# ADC.net
KiCad netlist of a schematic drawn in Altium Designer
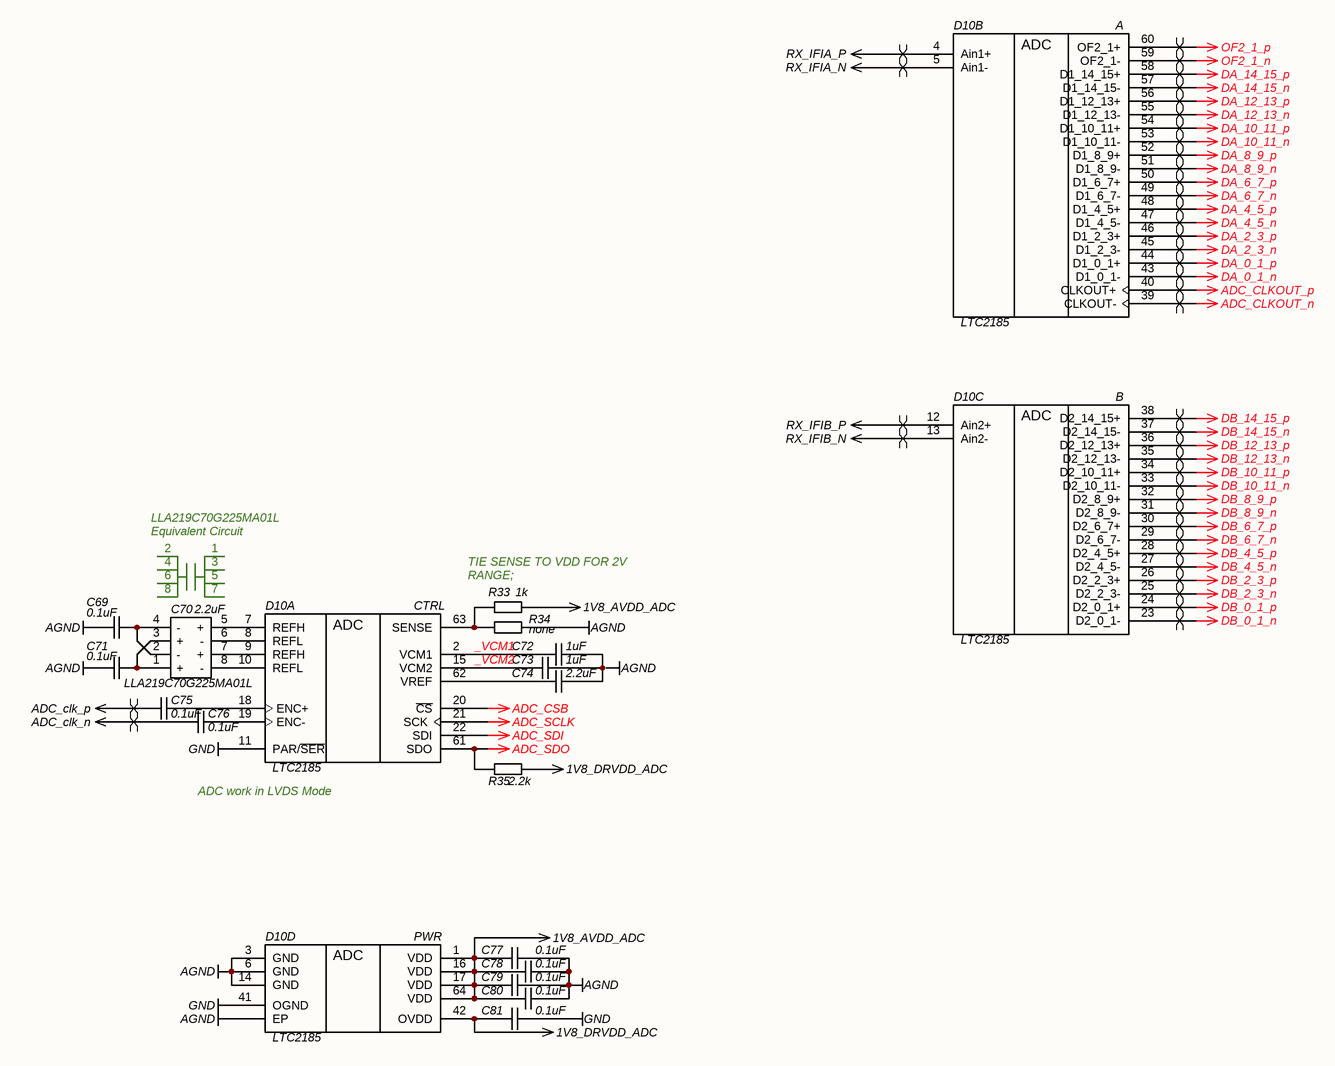
[diagram p0: ADC.SchDoc]

(export (version "E")
  (design (tool "Eeschema 10.0.6"))
  (components
    (comp (ref "C69")
      (value "0.1uF")
      (footprint "C0402")
      (description "SMD Capacitor")
      (fields (field (name "MANUFACTURER") "Murata") (field (name "TOLERANCE") "10%"))
      (libsource (lib "Kintex_SDR") (part "CAP"))
    )
    (comp (ref "C70")
      (value "LLA219C70G225MA01L")
      (footprint "DBLib:Murata_LLA219-0_1_MFG")
      (description "0805 2.2 uF 4 V ±20 % Tolerance X7S Surface Mount Multilayer Ceramic Capacitor")
      (fields
        (field (name "MANUFACTURER") "Murata")
        (field (name "TOLERANCE") "20%")
        (field (name "ALTIUM_VALUE") "2.2uF")
      )
      (libsource (lib "DBLib") (part "LLA219C70G225M"))
    )
    (comp (ref "C71")
      (value "0.1uF")
      (footprint "C0402")
      (description "SMD Capacitor")
      (fields (field (name "MANUFACTURER") "Murata") (field (name "TOLERANCE") "10%"))
      (libsource (lib "Kintex_SDR") (part "CAP"))
    )
    (comp (ref "C72")
      (value "1uF")
      (footprint "C0402")
      (description "SMD Capacitor")
      (fields (field (name "MANUFACTURER") "Murata") (field (name "TOLERANCE") "10%"))
      (libsource (lib "Kintex_SDR") (part "CAP"))
    )
    (comp (ref "C73")
      (value "1uF")
      (footprint "C0402")
      (description "SMD Capacitor")
      (fields (field (name "MANUFACTURER") "Murata") (field (name "TOLERANCE") "10%"))
      (libsource (lib "Kintex_SDR") (part "CAP"))
    )
    (comp (ref "C74")
      (value "2.2uF")
      (footprint "C0603")
      (description "SMD Capacitor")
      (fields (field (name "MANUFACTURER") "Murata") (field (name "TOLERANCE") "10%"))
      (libsource (lib "Kintex_SDR") (part "CAP"))
    )
    (comp (ref "C75")
      (value "0.1uF")
      (footprint "C0402")
      (description "SMD Capacitor")
      (fields (field (name "MANUFACTURER") "Murata") (field (name "TOLERANCE") "10%"))
      (libsource (lib "Kintex_SDR") (part "CAP"))
    )
    (comp (ref "C76")
      (value "0.1uF")
      (footprint "C0402")
      (description "SMD Capacitor")
      (fields (field (name "MANUFACTURER") "Murata") (field (name "TOLERANCE") "10%"))
      (libsource (lib "Kintex_SDR") (part "CAP"))
    )
    (comp (ref "C77")
      (value "0.1uF")
      (footprint "C0402")
      (description "SMD Capacitor")
      (fields (field (name "MANUFACTURER") "Murata") (field (name "TOLERANCE") "10%"))
      (libsource (lib "Kintex_SDR") (part "CAP"))
    )
    (comp (ref "C78")
      (value "0.1uF")
      (footprint "C0402")
      (description "SMD Capacitor")
      (fields (field (name "MANUFACTURER") "Murata") (field (name "TOLERANCE") "10%"))
      (libsource (lib "Kintex_SDR") (part "CAP"))
    )
    (comp (ref "C79")
      (value "0.1uF")
      (footprint "C0402")
      (description "SMD Capacitor")
      (fields (field (name "MANUFACTURER") "Murata") (field (name "TOLERANCE") "10%"))
      (libsource (lib "Kintex_SDR") (part "CAP"))
    )
    (comp (ref "C80")
      (value "0.1uF")
      (footprint "C0402")
      (description "SMD Capacitor")
      (fields (field (name "MANUFACTURER") "Murata") (field (name "TOLERANCE") "10%"))
      (libsource (lib "Kintex_SDR") (part "CAP"))
    )
    (comp (ref "C81")
      (value "0.1uF")
      (footprint "C0402")
      (description "SMD Capacitor")
      (fields (field (name "MANUFACTURER") "Murata") (field (name "TOLERANCE") "10%"))
      (libsource (lib "Kintex_SDR") (part "CAP"))
    )
    (comp (ref "D10")
      (value "LTC2185")
      (footprint "QFN-64")
      (description "Dual 16-Bit, 125Msps  Low Power 3V ADC")
      (fields (field (name "VOLTAGE") "Single 1.8V Supply"))
      (libsource (lib "") (part "LTC2185_1"))
    )
    (comp (ref "R33")
      (value "1k")
      (footprint "R0402")
      (description "SMD Resistor")
      (fields (field (name "POWER") "0.062 Wt") (field (name "TOLERANCE") "5%"))
      (libsource (lib "") (part "RES_1"))
    )
    (comp (ref "R34")
      (value "none")
      (footprint "R0402")
      (description "SMD Resistor")
      (fields
        (field (name "POWER") "0.062 Wt")
        (field (name "MANUFACTURER") "Panasonic Electronic Components")
      )
      (libsource (lib "") (part "RES_1"))
    )
    (comp (ref "R35")
      (value "2.2k")
      (footprint "R0402")
      (description "SMD Resistor")
      (fields (field (name "POWER") "0.062 Wt") (field (name "TOLERANCE") "5%"))
      (libsource (lib "Kintex_SDR") (part "RES"))
    )
  )
  (nets
    (net (code "1") (name "/_VCM1") (class "Default")
      (node (ref "C72") (pin "2") (pinfunction "2_2") (pintype "passive"))
      (node (ref "D10") (pin "2") (pinfunction "VCM1_2") (pintype "passive"))
    )
    (net (code "2") (name "/_VCM2") (class "Default")
      (node (ref "C73") (pin "2") (pinfunction "2_2") (pintype "passive"))
      (node (ref "D10") (pin "15") (pinfunction "VCM2_15") (pintype "passive"))
    )
    (net (code "3") (name "1V8_AVDD_ADC") (class "Default")
      (node (ref "C77") (pin "1") (pinfunction "1_1") (pintype "passive"))
      (node (ref "C78") (pin "1") (pinfunction "1_1") (pintype "passive"))
      (node (ref "C79") (pin "1") (pinfunction "1_1") (pintype "passive"))
      (node (ref "C80") (pin "1") (pinfunction "1_1") (pintype "passive"))
      (node (ref "D10") (pin "1") (pinfunction "VDD_1") (pintype "power_in"))
      (node (ref "D10") (pin "16") (pinfunction "VDD_16") (pintype "power_in"))
      (node (ref "D10") (pin "17") (pinfunction "VDD_17") (pintype "power_in"))
      (node (ref "D10") (pin "64") (pinfunction "VDD_64") (pintype "power_in"))
      (node (ref "R33") (pin "2") (pinfunction "2_2") (pintype "passive"))
    )
    (net (code "4") (name "1V8_DRVDD_ADC") (class "Default")
      (node (ref "C81") (pin "2") (pinfunction "2_2") (pintype "passive"))
      (node (ref "D10") (pin "42") (pinfunction "OVDD_42") (pintype "power_in"))
      (node (ref "R35") (pin "1") (pinfunction "1_1") (pintype "passive"))
    )
    (net (code "5") (name "ADC_CLKOUT_n") (class "Default")
      (node (ref "D10") (pin "39") (pinfunction "CLKOUT-_39") (pintype "passive"))
    )
    (net (code "6") (name "ADC_CLKOUT_p") (class "Default")
      (node (ref "D10") (pin "40") (pinfunction "CLKOUT+_40") (pintype "passive"))
    )
    (net (code "7") (name "ADC_CSB") (class "Default")
      (node (ref "D10") (pin "20") (pinfunction "~{CS}_20") (pintype "passive"))
    )
    (net (code "8") (name "ADC_SCLK") (class "Default")
      (node (ref "D10") (pin "21") (pinfunction "SCK_21") (pintype "passive"))
    )
    (net (code "9") (name "ADC_SDI") (class "Default")
      (node (ref "D10") (pin "22") (pinfunction "SDI_22") (pintype "passive"))
    )
    (net (code "10") (name "ADC_SDO") (class "Default")
      (node (ref "D10") (pin "61") (pinfunction "SDO_61") (pintype "passive"))
      (node (ref "R35") (pin "2") (pinfunction "2_2") (pintype "passive"))
    )
    (net (code "11") (name "ADC_clk_n") (class "Default")
      (node (ref "C76") (pin "2") (pinfunction "2_2") (pintype "passive"))
    )
    (net (code "12") (name "ADC_clk_p") (class "Default")
      (node (ref "C75") (pin "2") (pinfunction "2_2") (pintype "passive"))
    )
    (net (code "13") (name "AGND") (class "Default")
      (node (ref "C69") (pin "1") (pinfunction "1_1") (pintype "passive"))
      (node (ref "C71") (pin "1") (pinfunction "1_1") (pintype "passive"))
      (node (ref "C77") (pin "2") (pinfunction "2_2") (pintype "passive"))
      (node (ref "C78") (pin "2") (pinfunction "2_2") (pintype "passive"))
      (node (ref "C79") (pin "2") (pinfunction "2_2") (pintype "passive"))
      (node (ref "C80") (pin "2") (pinfunction "2_2") (pintype "passive"))
      (node (ref "D10") (pin "0") (pinfunction "EP_0") (pintype "power_in"))
      (node (ref "D10") (pin "14") (pinfunction "GND_14") (pintype "power_in"))
      (node (ref "D10") (pin "3") (pinfunction "GND_3") (pintype "power_in"))
      (node (ref "D10") (pin "6") (pinfunction "GND_6") (pintype "power_in"))
      (node (ref "R34") (pin "2") (pinfunction "2_2") (pintype "passive"))
    )
    (net (code "14") (name "DA_0_1_n") (class "Default")
      (node (ref "D10") (pin "43") (pinfunction "D1_0_1-_43") (pintype "passive"))
    )
    (net (code "15") (name "DA_0_1_p") (class "Default")
      (node (ref "D10") (pin "44") (pinfunction "D1_0_1+_44") (pintype "passive"))
    )
    (net (code "16") (name "DA_2_3_n") (class "Default")
      (node (ref "D10") (pin "45") (pinfunction "D1_2_3-_45") (pintype "passive"))
    )
    (net (code "17") (name "DA_2_3_p") (class "Default")
      (node (ref "D10") (pin "46") (pinfunction "D1_2_3+_46") (pintype "passive"))
    )
    (net (code "18") (name "DA_4_5_n") (class "Default")
      (node (ref "D10") (pin "47") (pinfunction "D1_4_5-_47") (pintype "passive"))
    )
    (net (code "19") (name "DA_4_5_p") (class "Default")
      (node (ref "D10") (pin "48") (pinfunction "D1_4_5+_48") (pintype "passive"))
    )
    (net (code "20") (name "DA_6_7_n") (class "Default")
      (node (ref "D10") (pin "49") (pinfunction "D1_6_7-_49") (pintype "passive"))
    )
    (net (code "21") (name "DA_6_7_p") (class "Default")
      (node (ref "D10") (pin "50") (pinfunction "D1_6_7+_50") (pintype "passive"))
    )
    (net (code "22") (name "DA_8_9_n") (class "Default")
      (node (ref "D10") (pin "51") (pinfunction "D1_8_9-_51") (pintype "passive"))
    )
    (net (code "23") (name "DA_8_9_p") (class "Default")
      (node (ref "D10") (pin "52") (pinfunction "D1_8_9+_52") (pintype "passive"))
    )
    (net (code "24") (name "DA_10_11_n") (class "Default")
      (node (ref "D10") (pin "53") (pinfunction "D1_10_11-_53") (pintype "passive"))
    )
    (net (code "25") (name "DA_10_11_p") (class "Default")
      (node (ref "D10") (pin "54") (pinfunction "D1_10_11+_54") (pintype "passive"))
    )
    (net (code "26") (name "DA_12_13_n") (class "Default")
      (node (ref "D10") (pin "55") (pinfunction "D1_12_13-_55") (pintype "passive"))
    )
    (net (code "27") (name "DA_12_13_p") (class "Default")
      (node (ref "D10") (pin "56") (pinfunction "D1_12_13+_56") (pintype "passive"))
    )
    (net (code "28") (name "DA_14_15_n") (class "Default")
      (node (ref "D10") (pin "57") (pinfunction "D1_14_15-_57") (pintype "passive"))
    )
    (net (code "29") (name "DA_14_15_p") (class "Default")
      (node (ref "D10") (pin "58") (pinfunction "D1_14_15+_58") (pintype "passive"))
    )
    (net (code "30") (name "DB_0_1_n") (class "Default")
      (node (ref "D10") (pin "23") (pinfunction "D2_0_1-_23") (pintype "passive"))
    )
    (net (code "31") (name "DB_0_1_p") (class "Default")
      (node (ref "D10") (pin "24") (pinfunction "D2_0_1+_24") (pintype "passive"))
    )
    (net (code "32") (name "DB_2_3_n") (class "Default")
      (node (ref "D10") (pin "25") (pinfunction "D2_2_3-_25") (pintype "passive"))
    )
    (net (code "33") (name "DB_2_3_p") (class "Default")
      (node (ref "D10") (pin "26") (pinfunction "D2_2_3+_26") (pintype "passive"))
    )
    (net (code "34") (name "DB_4_5_n") (class "Default")
      (node (ref "D10") (pin "27") (pinfunction "D2_4_5-_27") (pintype "passive"))
    )
    (net (code "35") (name "DB_4_5_p") (class "Default")
      (node (ref "D10") (pin "28") (pinfunction "D2_4_5+_28") (pintype "passive"))
    )
    (net (code "36") (name "DB_6_7_n") (class "Default")
      (node (ref "D10") (pin "29") (pinfunction "D2_6_7-_29") (pintype "passive"))
    )
    (net (code "37") (name "DB_6_7_p") (class "Default")
      (node (ref "D10") (pin "30") (pinfunction "D2_6_7+_30") (pintype "passive"))
    )
    (net (code "38") (name "DB_8_9_n") (class "Default")
      (node (ref "D10") (pin "31") (pinfunction "D2_8_9-_31") (pintype "passive"))
    )
    (net (code "39") (name "DB_8_9_p") (class "Default")
      (node (ref "D10") (pin "32") (pinfunction "D2_8_9+_32") (pintype "passive"))
    )
    (net (code "40") (name "DB_10_11_n") (class "Default")
      (node (ref "D10") (pin "33") (pinfunction "D2_10_11-_33") (pintype "passive"))
    )
    (net (code "41") (name "DB_10_11_p") (class "Default")
      (node (ref "D10") (pin "34") (pinfunction "D2_10_11+_34") (pintype "passive"))
    )
    (net (code "42") (name "DB_12_13_n") (class "Default")
      (node (ref "D10") (pin "35") (pinfunction "D2_12_13-_35") (pintype "passive"))
    )
    (net (code "43") (name "DB_12_13_p") (class "Default")
      (node (ref "D10") (pin "36") (pinfunction "D2_12_13+_36") (pintype "passive"))
    )
    (net (code "44") (name "DB_14_15_n") (class "Default")
      (node (ref "D10") (pin "37") (pinfunction "D2_14_15-_37") (pintype "passive"))
    )
    (net (code "45") (name "DB_14_15_p") (class "Default")
      (node (ref "D10") (pin "38") (pinfunction "D2_14_15+_38") (pintype "passive"))
    )
    (net (code "46") (name "GND") (class "Default")
      (node (ref "C81") (pin "1") (pinfunction "1_1") (pintype "passive"))
      (node (ref "D10") (pin "11") (pinfunction "PAR/~{SER}_11") (pintype "passive"))
      (node (ref "D10") (pin "41") (pinfunction "OGND_41") (pintype "power_in"))
    )
    (net (code "47") (name "Net-(C69-Pad2)") (class "Default")
      (node (ref "C69") (pin "2") (pinfunction "2_2") (pintype "passive"))
      (node (ref "C70") (pin "2") (pinfunction "-_2") (pintype "passive"))
      (node (ref "C70") (pin "4") (pinfunction "-_4") (pintype "passive"))
    )
    (net (code "48") (name "Net-(C70-+-Pad1)") (class "Default")
      (node (ref "C70") (pin "1") (pinfunction "+_1") (pintype "passive"))
      (node (ref "C70") (pin "3") (pinfunction "+_3") (pintype "passive"))
      (node (ref "C71") (pin "2") (pinfunction "2_2") (pintype "passive"))
    )
    (net (code "49") (name "Net-(C70-+-Pad5)") (class "Default")
      (node (ref "C70") (pin "5") (pinfunction "+_5") (pintype "passive"))
      (node (ref "D10") (pin "7") (pinfunction "REFH_7") (pintype "passive"))
    )
    (net (code "50") (name "Net-(C70-+-Pad7)") (class "Default")
      (node (ref "C70") (pin "7") (pinfunction "+_7") (pintype "passive"))
      (node (ref "D10") (pin "9") (pinfunction "REFH_9") (pintype "passive"))
    )
    (net (code "51") (name "Net-(C70---Pad6)") (class "Default")
      (node (ref "C70") (pin "6") (pinfunction "-_6") (pintype "passive"))
      (node (ref "D10") (pin "8") (pinfunction "REFL_8") (pintype "passive"))
    )
    (net (code "52") (name "Net-(C70---Pad8)") (class "Default")
      (node (ref "C70") (pin "8") (pinfunction "-_8") (pintype "passive"))
      (node (ref "D10") (pin "10") (pinfunction "REFL_10") (pintype "passive"))
    )
    (net (code "53") (name "Net-(C72-Pad1)") (class "Default")
      (node (ref "C72") (pin "1") (pinfunction "1_1") (pintype "passive"))
      (node (ref "C73") (pin "1") (pinfunction "1_1") (pintype "passive"))
      (node (ref "C74") (pin "1") (pinfunction "1_1") (pintype "passive"))
    )
    (net (code "54") (name "Net-(D10A-ENC+)") (class "Default")
      (node (ref "C75") (pin "1") (pinfunction "1_1") (pintype "passive"))
      (node (ref "D10") (pin "18") (pinfunction "ENC+_18") (pintype "passive"))
    )
    (net (code "55") (name "Net-(D10A-ENC-)") (class "Default")
      (node (ref "C76") (pin "1") (pinfunction "1_1") (pintype "passive"))
      (node (ref "D10") (pin "19") (pinfunction "ENC-_19") (pintype "passive"))
    )
    (net (code "56") (name "Net-(D10A-SENSE)") (class "Default")
      (node (ref "D10") (pin "63") (pinfunction "SENSE_63") (pintype "passive"))
      (node (ref "R33") (pin "1") (pinfunction "1_1") (pintype "passive"))
      (node (ref "R34") (pin "1") (pinfunction "1_1") (pintype "passive"))
    )
    (net (code "57") (name "Net-(D10A-VREF)") (class "Default")
      (node (ref "C74") (pin "2") (pinfunction "2_2") (pintype "passive"))
      (node (ref "D10") (pin "62") (pinfunction "VREF_62") (pintype "passive"))
    )
    (net (code "58") (name "OF2_1_n") (class "Default")
      (node (ref "D10") (pin "59") (pinfunction "OF2_1-_59") (pintype "passive"))
    )
    (net (code "59") (name "OF2_1_p") (class "Default")
      (node (ref "D10") (pin "60") (pinfunction "OF2_1+_60") (pintype "passive"))
    )
    (net (code "60") (name "RX_IFIA_N") (class "Default")
      (node (ref "D10") (pin "5") (pinfunction "Ain1-_5") (pintype "passive"))
    )
    (net (code "61") (name "RX_IFIA_P") (class "Default")
      (node (ref "D10") (pin "4") (pinfunction "Ain1+_4") (pintype "passive"))
    )
    (net (code "62") (name "RX_IFIB_N") (class "Default")
      (node (ref "D10") (pin "13") (pinfunction "Ain2-_13") (pintype "passive"))
    )
    (net (code "63") (name "RX_IFIB_P") (class "Default")
      (node (ref "D10") (pin "12") (pinfunction "Ain2+_12") (pintype "passive"))
    )
  )
)
